# Sh_opto_out.net
KiCad netlist of a schematic drawn in Altium Designer
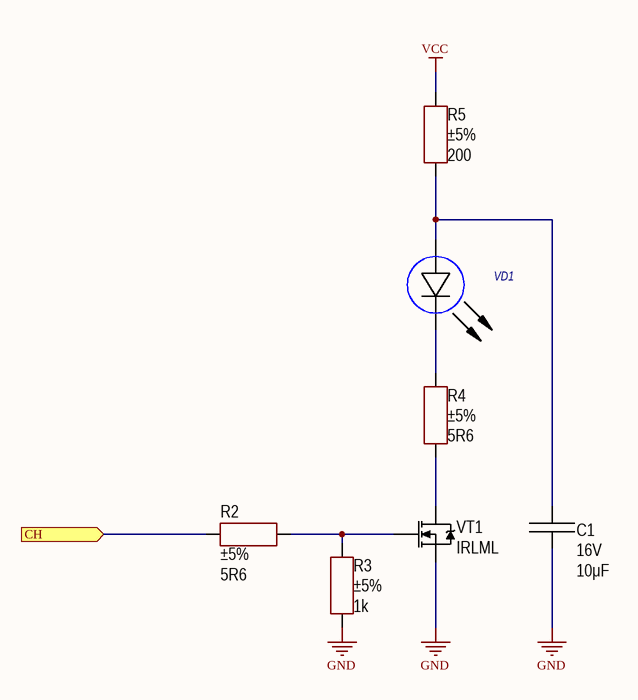
[diagram p0: Sh_opto_out.SchDoc]

(export (version "E")
  (design (tool "Eeschema 10.0.6"))
  (components
    (comp (ref "C1")
      (value "10μF")
      (footprint "CAP: 0805")
      (fields
        (field (name "MANUFACTURER") "Yageo")
        (field (name "PARTNUMBER") "CC0805KRX7R7BB104")
        (field (name "VALUEMANUFACTURERPARTNUMBER") "Ceramic capacitor, 10μF, X7R, ±10%, 16V, 0805, -55...+125°C")
        (field (name "VOLTAGE") "16V")
      )
      (libsource (lib "capacitor") (part "Ceramic_0805"))
    )
    (comp (ref "R2")
      (value "5R6")
      (footprint "RES: 1206")
      (fields
        (field (name "MANUFACTURER") "Yageo")
        (field (name "PARTNUMBER") "RC1206JR-07100RL")
        (field (name "VALUEMANUFACTURERPARTNUMBER") "Resistor film, 5R6, ±5%, 1206, 0.25W, -55...+125°C")
        (field (name "TOLERANCE") "±5%")
      )
      (libsource (lib "resistor") (part "Resistor_1206"))
    )
    (comp (ref "R3")
      (value "1k")
      (footprint "RES: 0805")
      (fields
        (field (name "MANUFACTURER") "Yageo")
        (field (name "PARTNUMBER") "RC0805JR-07100RL")
        (field (name "VALUEMANUFACTURERPARTNUMBER") "Resistor film, 1k, ±5%, 0805, 0.125W, -55...+125°C")
        (field (name "TOLERANCE") "±5%")
      )
      (libsource (lib "resistor") (part "Resistor_0805"))
    )
    (comp (ref "R4")
      (value "5R6")
      (footprint "RES: 0805")
      (fields
        (field (name "MANUFACTURER") "Yageo")
        (field (name "PARTNUMBER") "RC0805JR-07100RL")
        (field (name "VALUEMANUFACTURERPARTNUMBER") "Resistor film, 5R6, ±5%, 0805, 0.125W, -55...+125°C")
        (field (name "TOLERANCE") "±5%")
      )
      (libsource (lib "resistor") (part "Resistor_0805"))
    )
    (comp (ref "R5")
      (value "200")
      (footprint "RES: 0805")
      (fields
        (field (name "MANUFACTURER") "Yageo")
        (field (name "PARTNUMBER") "RC0805JR-07100RL")
        (field (name "VALUEMANUFACTURERPARTNUMBER") "Resistor film, 200, ±5%, 0805, 0.125W, -55...+125°C")
        (field (name "TOLERANCE") "±5%")
      )
      (libsource (lib "resistor") (part "Resistor_0805"))
    )
    (comp (ref "VD1") (value "SHF757") (footprint "LED: SFH757") (libsource (lib "diode") (part "SHF757")))
    (comp (ref "VT1")
      (value "~")
      (footprint "SOT23")
      (fields
        (field (name "MANUFACTURER") "Infineon Technologies")
        (field (name "VALUEMANUFACTURERPARTNUMBER") "MOSFET N-channel transistor, 80V, 7A, 9.1nC, 2.5W, 34mOhm, 756pF, 8-TDSON, -55...+150°C")
        (field (name "PARTNUMBER") "IRLML")
      )
      (libsource (lib "transistor") (part "MOSFET_N_132"))
    )
  )
  (nets
    (net (code "1") (name "/CH") (class "Default")
      (node (ref "R2") (pin "1") (pinfunction "1_1") (pintype "passive"))
    )
    (net (code "2") (name "GND") (class "Default")
      (node (ref "C1") (pin "1") (pinfunction "1_1") (pintype "passive"))
      (node (ref "R3") (pin "1") (pinfunction "1_1") (pintype "passive"))
      (node (ref "VT1") (pin "2") (pinfunction "S_2") (pintype "passive"))
    )
    (net (code "3") (name "Net-(VD1-A)") (class "Default")
      (node (ref "C1") (pin "2") (pinfunction "2_2") (pintype "passive"))
      (node (ref "R5") (pin "1") (pinfunction "1_1") (pintype "passive"))
      (node (ref "VD1") (pin "1") (pinfunction "A_1") (pintype "passive"))
    )
    (net (code "4") (name "Net-(VD1-C)") (class "Default")
      (node (ref "R4") (pin "2") (pinfunction "2_2") (pintype "passive"))
      (node (ref "VD1") (pin "2") (pinfunction "C_2") (pintype "passive"))
    )
    (net (code "5") (name "Net-(VT1-D)") (class "Default")
      (node (ref "R4") (pin "1") (pinfunction "1_1") (pintype "passive"))
      (node (ref "VT1") (pin "3") (pinfunction "D_3") (pintype "passive"))
    )
    (net (code "6") (name "Net-(VT1-G)") (class "Default")
      (node (ref "R2") (pin "2") (pinfunction "2_2") (pintype "passive"))
      (node (ref "R3") (pin "2") (pinfunction "2_2") (pintype "passive"))
      (node (ref "VT1") (pin "1") (pinfunction "G_1") (pintype "passive"))
    )
    (net (code "7") (name "VCC") (class "Default")
      (node (ref "R5") (pin "2") (pinfunction "2_2") (pintype "passive"))
    )
  )
)
